# Backplane-2.net
KiCad netlist of a schematic drawn in EAGLE
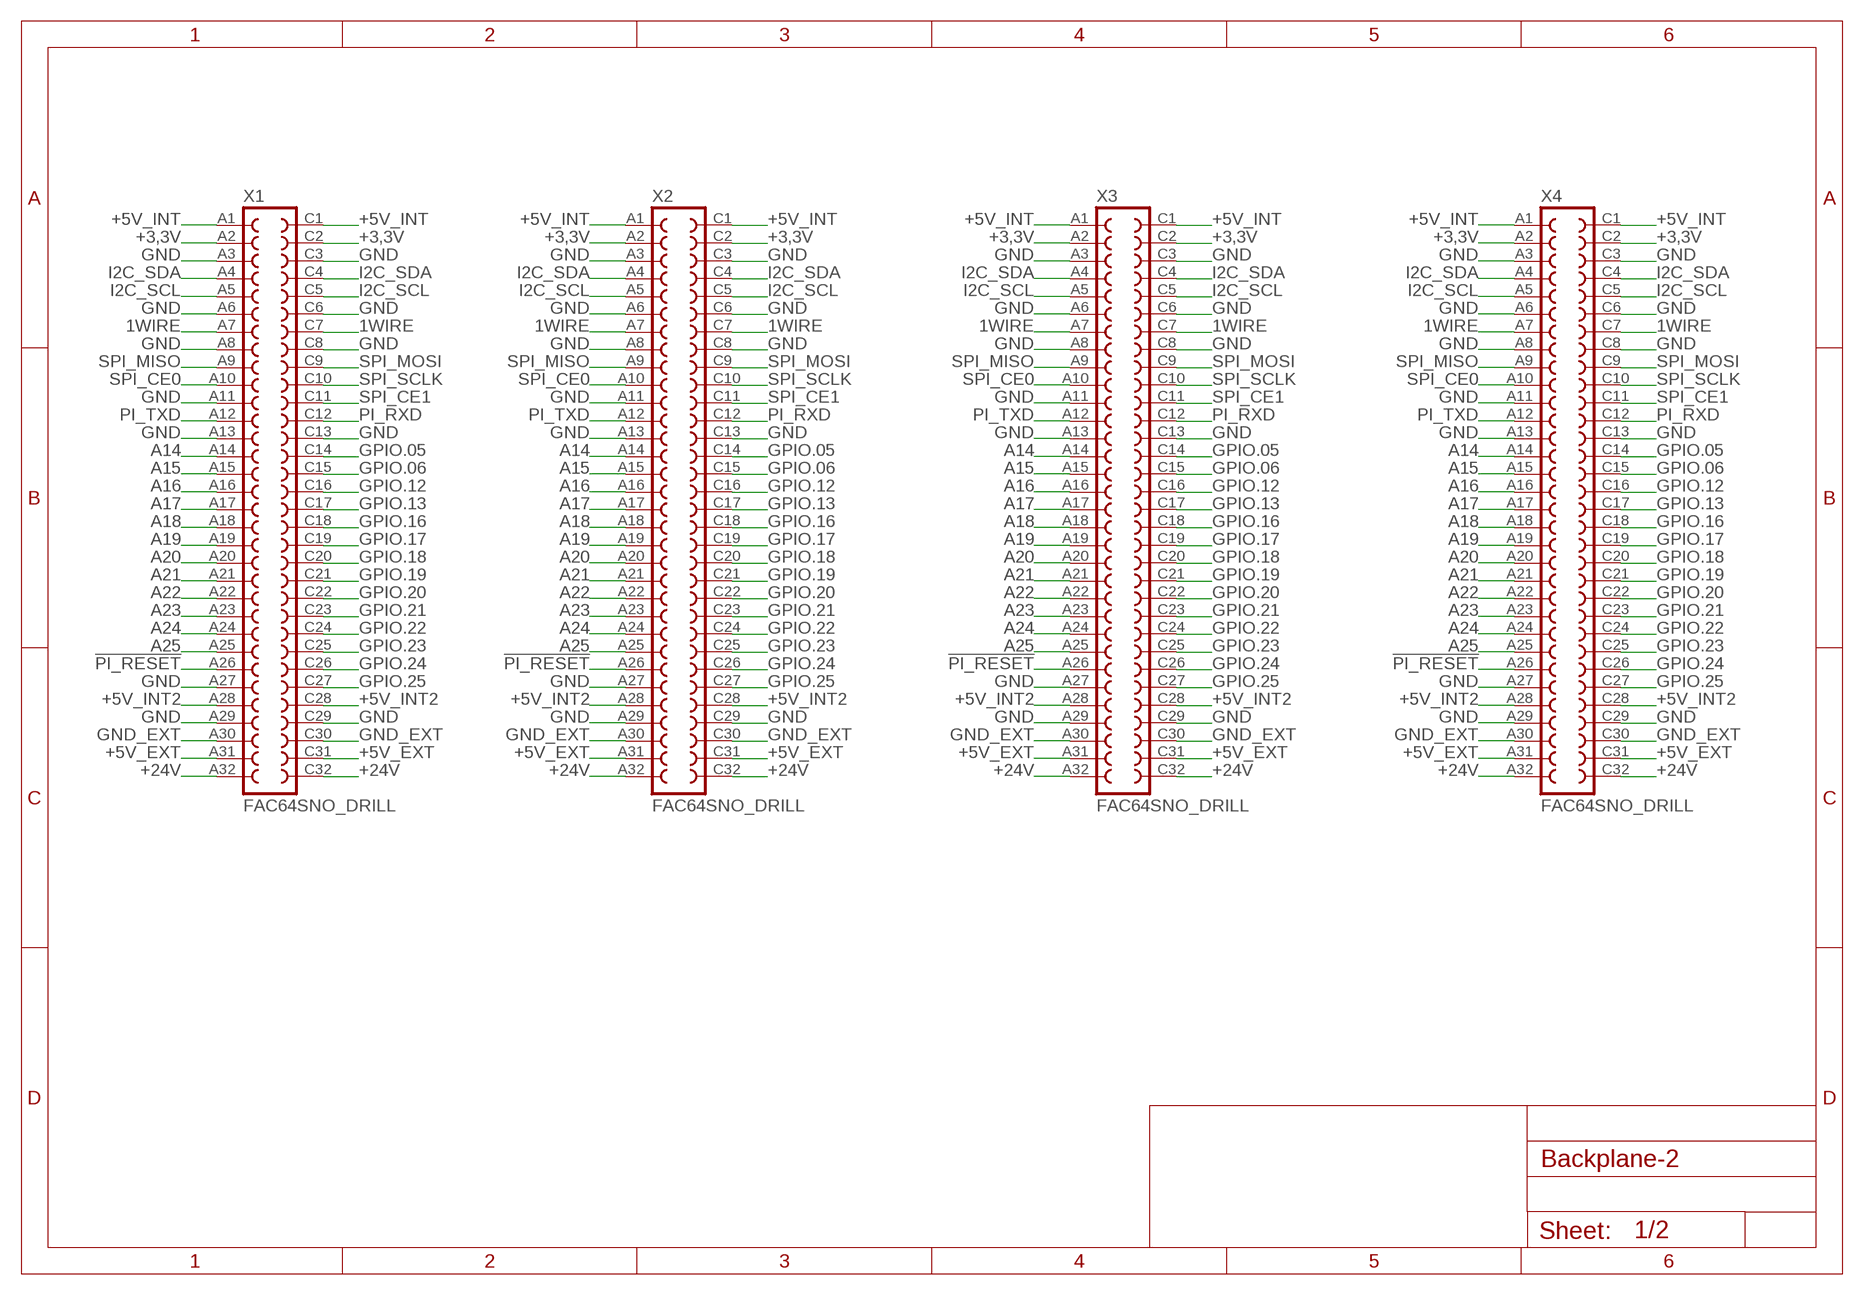
[diagram p0: schematic, sheet 1]
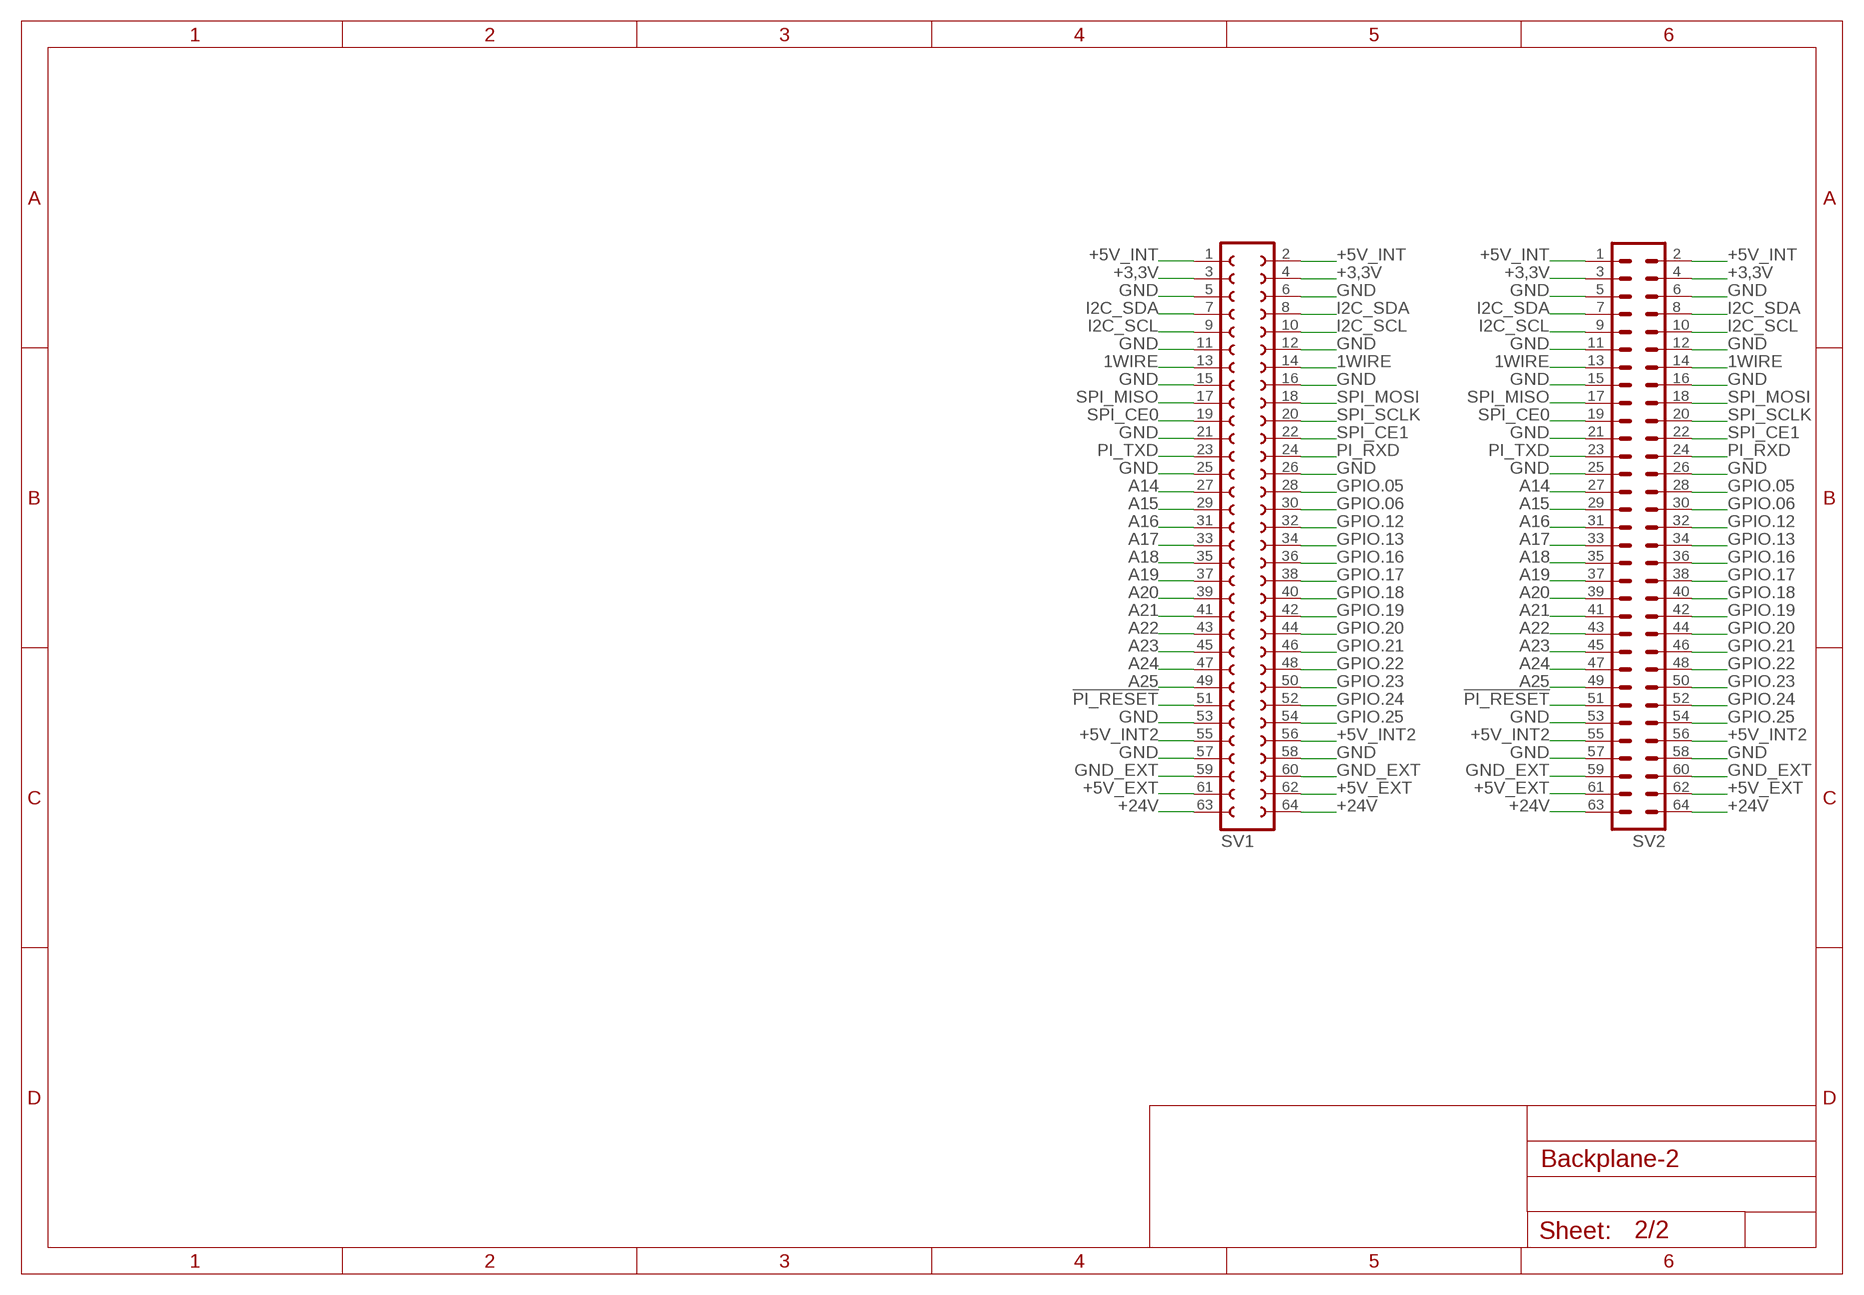
[diagram p1: schematic, sheet 2]

(export (version "E")
  (design (tool "Eeschema 10.0.6"))
  (components
    (comp (ref "SV1")
      (value "FE32-2W")
      (footprint "eagle-import:FE32-2W")
      (libsource (lib "eagle-import") (part "FE32-2W"))
    )
    (comp (ref "SV2")
      (value "MA32-2W")
      (footprint "eagle-import:MA32-2W")
      (libsource (lib "eagle-import") (part "MA32-2W"))
    )
    (comp (ref "X1")
      (value "FAC64SNO_DRILL")
      (footprint "eagle-import:FAC64S_NO_DRILL")
      (libsource (lib "eagle-import") (part "FAC64SNO_DRILL"))
    )
    (comp (ref "X2")
      (value "FAC64SNO_DRILL")
      (footprint "eagle-import:FAC64S_NO_DRILL")
      (libsource (lib "eagle-import") (part "FAC64SNO_DRILL"))
    )
    (comp (ref "X3")
      (value "FAC64SNO_DRILL")
      (footprint "eagle-import:FAC64S_NO_DRILL")
      (libsource (lib "eagle-import") (part "FAC64SNO_DRILL"))
    )
    (comp (ref "X4")
      (value "FAC64SNO_DRILL")
      (footprint "eagle-import:FAC64S_NO_DRILL")
      (libsource (lib "eagle-import") (part "FAC64SNO_DRILL"))
    )
  )
  (nets
    (net (code "1") (name "+3,3V") (class "Default")
      (node (ref "SV1") (pin "3") (pinfunction "3_3") (pintype "passive"))
      (node (ref "SV1") (pin "4") (pinfunction "4_4") (pintype "passive"))
      (node (ref "SV2") (pin "3") (pinfunction "3_3") (pintype "passive"))
      (node (ref "SV2") (pin "4") (pinfunction "4_4") (pintype "passive"))
      (node (ref "X1") (pin "A2") (pinfunction "A2_A2") (pintype "passive"))
      (node (ref "X1") (pin "C2") (pinfunction "C2_C2") (pintype "passive"))
      (node (ref "X2") (pin "A2") (pinfunction "A2_A2") (pintype "passive"))
      (node (ref "X2") (pin "C2") (pinfunction "C2_C2") (pintype "passive"))
      (node (ref "X3") (pin "A2") (pinfunction "A2_A2") (pintype "passive"))
      (node (ref "X3") (pin "C2") (pinfunction "C2_C2") (pintype "passive"))
      (node (ref "X4") (pin "A2") (pinfunction "A2_A2") (pintype "passive"))
      (node (ref "X4") (pin "C2") (pinfunction "C2_C2") (pintype "passive"))
    )
    (net (code "2") (name "+5V_EXT") (class "Default")
      (node (ref "SV1") (pin "61") (pinfunction "61_61") (pintype "passive"))
      (node (ref "SV1") (pin "62") (pinfunction "62_62") (pintype "passive"))
      (node (ref "SV2") (pin "61") (pinfunction "61_61") (pintype "passive"))
      (node (ref "SV2") (pin "62") (pinfunction "62_62") (pintype "passive"))
      (node (ref "X1") (pin "A31") (pinfunction "A31_A31") (pintype "passive"))
      (node (ref "X1") (pin "C31") (pinfunction "C31_C31") (pintype "passive"))
      (node (ref "X2") (pin "A31") (pinfunction "A31_A31") (pintype "passive"))
      (node (ref "X2") (pin "C31") (pinfunction "C31_C31") (pintype "passive"))
      (node (ref "X3") (pin "A31") (pinfunction "A31_A31") (pintype "passive"))
      (node (ref "X3") (pin "C31") (pinfunction "C31_C31") (pintype "passive"))
      (node (ref "X4") (pin "A31") (pinfunction "A31_A31") (pintype "passive"))
      (node (ref "X4") (pin "C31") (pinfunction "C31_C31") (pintype "passive"))
    )
    (net (code "3") (name "+5V_INT") (class "Default")
      (node (ref "SV1") (pin "1") (pinfunction "1_1") (pintype "passive"))
      (node (ref "SV1") (pin "2") (pinfunction "2_2") (pintype "passive"))
      (node (ref "SV2") (pin "1") (pinfunction "1_1") (pintype "passive"))
      (node (ref "SV2") (pin "2") (pinfunction "2_2") (pintype "passive"))
      (node (ref "X1") (pin "A1") (pinfunction "A1_A1") (pintype "passive"))
      (node (ref "X1") (pin "C1") (pinfunction "C1_C1") (pintype "passive"))
      (node (ref "X2") (pin "A1") (pinfunction "A1_A1") (pintype "passive"))
      (node (ref "X2") (pin "C1") (pinfunction "C1_C1") (pintype "passive"))
      (node (ref "X3") (pin "A1") (pinfunction "A1_A1") (pintype "passive"))
      (node (ref "X3") (pin "C1") (pinfunction "C1_C1") (pintype "passive"))
      (node (ref "X4") (pin "A1") (pinfunction "A1_A1") (pintype "passive"))
      (node (ref "X4") (pin "C1") (pinfunction "C1_C1") (pintype "passive"))
    )
    (net (code "4") (name "+5V_INT2") (class "Default")
      (node (ref "SV1") (pin "55") (pinfunction "55_55") (pintype "passive"))
      (node (ref "SV1") (pin "56") (pinfunction "56_56") (pintype "passive"))
      (node (ref "SV2") (pin "55") (pinfunction "55_55") (pintype "passive"))
      (node (ref "SV2") (pin "56") (pinfunction "56_56") (pintype "passive"))
      (node (ref "X1") (pin "A28") (pinfunction "A28_A28") (pintype "passive"))
      (node (ref "X1") (pin "C28") (pinfunction "C28_C28") (pintype "passive"))
      (node (ref "X2") (pin "A28") (pinfunction "A28_A28") (pintype "passive"))
      (node (ref "X2") (pin "C28") (pinfunction "C28_C28") (pintype "passive"))
      (node (ref "X3") (pin "A28") (pinfunction "A28_A28") (pintype "passive"))
      (node (ref "X3") (pin "C28") (pinfunction "C28_C28") (pintype "passive"))
      (node (ref "X4") (pin "A28") (pinfunction "A28_A28") (pintype "passive"))
      (node (ref "X4") (pin "C28") (pinfunction "C28_C28") (pintype "passive"))
    )
    (net (code "5") (name "+24V") (class "Default")
      (node (ref "SV1") (pin "63") (pinfunction "63_63") (pintype "passive"))
      (node (ref "SV1") (pin "64") (pinfunction "64_64") (pintype "passive"))
      (node (ref "SV2") (pin "63") (pinfunction "63_63") (pintype "passive"))
      (node (ref "SV2") (pin "64") (pinfunction "64_64") (pintype "passive"))
      (node (ref "X1") (pin "A32") (pinfunction "A32_A32") (pintype "passive"))
      (node (ref "X1") (pin "C32") (pinfunction "C32_C32") (pintype "passive"))
      (node (ref "X2") (pin "A32") (pinfunction "A32_A32") (pintype "passive"))
      (node (ref "X2") (pin "C32") (pinfunction "C32_C32") (pintype "passive"))
      (node (ref "X3") (pin "A32") (pinfunction "A32_A32") (pintype "passive"))
      (node (ref "X3") (pin "C32") (pinfunction "C32_C32") (pintype "passive"))
      (node (ref "X4") (pin "A32") (pinfunction "A32_A32") (pintype "passive"))
      (node (ref "X4") (pin "C32") (pinfunction "C32_C32") (pintype "passive"))
    )
    (net (code "6") (name "1WIRE") (class "Default")
      (node (ref "SV1") (pin "13") (pinfunction "13_13") (pintype "passive"))
      (node (ref "SV1") (pin "14") (pinfunction "14_14") (pintype "passive"))
      (node (ref "SV2") (pin "13") (pinfunction "13_13") (pintype "passive"))
      (node (ref "SV2") (pin "14") (pinfunction "14_14") (pintype "passive"))
      (node (ref "X1") (pin "A7") (pinfunction "A7_A7") (pintype "passive"))
      (node (ref "X1") (pin "C7") (pinfunction "C7_C7") (pintype "passive"))
      (node (ref "X2") (pin "A7") (pinfunction "A7_A7") (pintype "passive"))
      (node (ref "X2") (pin "C7") (pinfunction "C7_C7") (pintype "passive"))
      (node (ref "X3") (pin "A7") (pinfunction "A7_A7") (pintype "passive"))
      (node (ref "X3") (pin "C7") (pinfunction "C7_C7") (pintype "passive"))
      (node (ref "X4") (pin "A7") (pinfunction "A7_A7") (pintype "passive"))
      (node (ref "X4") (pin "C7") (pinfunction "C7_C7") (pintype "passive"))
    )
    (net (code "7") (name "A14") (class "Default")
      (node (ref "SV1") (pin "27") (pinfunction "27_27") (pintype "passive"))
      (node (ref "SV2") (pin "27") (pinfunction "27_27") (pintype "passive"))
      (node (ref "X1") (pin "A14") (pinfunction "A14_A14") (pintype "passive"))
      (node (ref "X2") (pin "A14") (pinfunction "A14_A14") (pintype "passive"))
      (node (ref "X3") (pin "A14") (pinfunction "A14_A14") (pintype "passive"))
      (node (ref "X4") (pin "A14") (pinfunction "A14_A14") (pintype "passive"))
    )
    (net (code "8") (name "A15") (class "Default")
      (node (ref "SV1") (pin "29") (pinfunction "29_29") (pintype "passive"))
      (node (ref "SV2") (pin "29") (pinfunction "29_29") (pintype "passive"))
      (node (ref "X1") (pin "A15") (pinfunction "A15_A15") (pintype "passive"))
      (node (ref "X2") (pin "A15") (pinfunction "A15_A15") (pintype "passive"))
      (node (ref "X3") (pin "A15") (pinfunction "A15_A15") (pintype "passive"))
      (node (ref "X4") (pin "A15") (pinfunction "A15_A15") (pintype "passive"))
    )
    (net (code "9") (name "A16") (class "Default")
      (node (ref "SV1") (pin "31") (pinfunction "31_31") (pintype "passive"))
      (node (ref "SV2") (pin "31") (pinfunction "31_31") (pintype "passive"))
      (node (ref "X1") (pin "A16") (pinfunction "A16_A16") (pintype "passive"))
      (node (ref "X2") (pin "A16") (pinfunction "A16_A16") (pintype "passive"))
      (node (ref "X3") (pin "A16") (pinfunction "A16_A16") (pintype "passive"))
      (node (ref "X4") (pin "A16") (pinfunction "A16_A16") (pintype "passive"))
    )
    (net (code "10") (name "A17") (class "Default")
      (node (ref "SV1") (pin "33") (pinfunction "33_33") (pintype "passive"))
      (node (ref "SV2") (pin "33") (pinfunction "33_33") (pintype "passive"))
      (node (ref "X1") (pin "A17") (pinfunction "A17_A17") (pintype "passive"))
      (node (ref "X2") (pin "A17") (pinfunction "A17_A17") (pintype "passive"))
      (node (ref "X3") (pin "A17") (pinfunction "A17_A17") (pintype "passive"))
      (node (ref "X4") (pin "A17") (pinfunction "A17_A17") (pintype "passive"))
    )
    (net (code "11") (name "A18") (class "Default")
      (node (ref "SV1") (pin "35") (pinfunction "35_35") (pintype "passive"))
      (node (ref "SV2") (pin "35") (pinfunction "35_35") (pintype "passive"))
      (node (ref "X1") (pin "A18") (pinfunction "A18_A18") (pintype "passive"))
      (node (ref "X2") (pin "A18") (pinfunction "A18_A18") (pintype "passive"))
      (node (ref "X3") (pin "A18") (pinfunction "A18_A18") (pintype "passive"))
      (node (ref "X4") (pin "A18") (pinfunction "A18_A18") (pintype "passive"))
    )
    (net (code "12") (name "A19") (class "Default")
      (node (ref "SV1") (pin "37") (pinfunction "37_37") (pintype "passive"))
      (node (ref "SV2") (pin "37") (pinfunction "37_37") (pintype "passive"))
      (node (ref "X1") (pin "A19") (pinfunction "A19_A19") (pintype "passive"))
      (node (ref "X2") (pin "A19") (pinfunction "A19_A19") (pintype "passive"))
      (node (ref "X3") (pin "A19") (pinfunction "A19_A19") (pintype "passive"))
      (node (ref "X4") (pin "A19") (pinfunction "A19_A19") (pintype "passive"))
    )
    (net (code "13") (name "A20") (class "Default")
      (node (ref "SV1") (pin "39") (pinfunction "39_39") (pintype "passive"))
      (node (ref "SV2") (pin "39") (pinfunction "39_39") (pintype "passive"))
      (node (ref "X1") (pin "A20") (pinfunction "A20_A20") (pintype "passive"))
      (node (ref "X2") (pin "A20") (pinfunction "A20_A20") (pintype "passive"))
      (node (ref "X3") (pin "A20") (pinfunction "A20_A20") (pintype "passive"))
      (node (ref "X4") (pin "A20") (pinfunction "A20_A20") (pintype "passive"))
    )
    (net (code "14") (name "A21") (class "Default")
      (node (ref "SV1") (pin "41") (pinfunction "41_41") (pintype "passive"))
      (node (ref "SV2") (pin "41") (pinfunction "41_41") (pintype "passive"))
      (node (ref "X1") (pin "A21") (pinfunction "A21_A21") (pintype "passive"))
      (node (ref "X2") (pin "A21") (pinfunction "A21_A21") (pintype "passive"))
      (node (ref "X3") (pin "A21") (pinfunction "A21_A21") (pintype "passive"))
      (node (ref "X4") (pin "A21") (pinfunction "A21_A21") (pintype "passive"))
    )
    (net (code "15") (name "A22") (class "Default")
      (node (ref "SV1") (pin "43") (pinfunction "43_43") (pintype "passive"))
      (node (ref "SV2") (pin "43") (pinfunction "43_43") (pintype "passive"))
      (node (ref "X1") (pin "A22") (pinfunction "A22_A22") (pintype "passive"))
      (node (ref "X2") (pin "A22") (pinfunction "A22_A22") (pintype "passive"))
      (node (ref "X3") (pin "A22") (pinfunction "A22_A22") (pintype "passive"))
      (node (ref "X4") (pin "A22") (pinfunction "A22_A22") (pintype "passive"))
    )
    (net (code "16") (name "A23") (class "Default")
      (node (ref "SV1") (pin "45") (pinfunction "45_45") (pintype "passive"))
      (node (ref "SV2") (pin "45") (pinfunction "45_45") (pintype "passive"))
      (node (ref "X1") (pin "A23") (pinfunction "A23_A23") (pintype "passive"))
      (node (ref "X2") (pin "A23") (pinfunction "A23_A23") (pintype "passive"))
      (node (ref "X3") (pin "A23") (pinfunction "A23_A23") (pintype "passive"))
      (node (ref "X4") (pin "A23") (pinfunction "A23_A23") (pintype "passive"))
    )
    (net (code "17") (name "A24") (class "Default")
      (node (ref "SV1") (pin "47") (pinfunction "47_47") (pintype "passive"))
      (node (ref "SV2") (pin "47") (pinfunction "47_47") (pintype "passive"))
      (node (ref "X1") (pin "A24") (pinfunction "A24_A24") (pintype "passive"))
      (node (ref "X2") (pin "A24") (pinfunction "A24_A24") (pintype "passive"))
      (node (ref "X3") (pin "A24") (pinfunction "A24_A24") (pintype "passive"))
      (node (ref "X4") (pin "A24") (pinfunction "A24_A24") (pintype "passive"))
    )
    (net (code "18") (name "A25") (class "Default")
      (node (ref "SV1") (pin "49") (pinfunction "49_49") (pintype "passive"))
      (node (ref "SV2") (pin "49") (pinfunction "49_49") (pintype "passive"))
      (node (ref "X1") (pin "A25") (pinfunction "A25_A25") (pintype "passive"))
      (node (ref "X2") (pin "A25") (pinfunction "A25_A25") (pintype "passive"))
      (node (ref "X3") (pin "A25") (pinfunction "A25_A25") (pintype "passive"))
      (node (ref "X4") (pin "A25") (pinfunction "A25_A25") (pintype "passive"))
    )
    (net (code "19") (name "GND") (class "Default")
      (node (ref "SV1") (pin "11") (pinfunction "11_11") (pintype "passive"))
      (node (ref "SV1") (pin "12") (pinfunction "12_12") (pintype "passive"))
      (node (ref "SV1") (pin "15") (pinfunction "15_15") (pintype "passive"))
      (node (ref "SV1") (pin "16") (pinfunction "16_16") (pintype "passive"))
      (node (ref "SV1") (pin "21") (pinfunction "21_21") (pintype "passive"))
      (node (ref "SV1") (pin "25") (pinfunction "25_25") (pintype "passive"))
      (node (ref "SV1") (pin "26") (pinfunction "26_26") (pintype "passive"))
      (node (ref "SV1") (pin "5") (pinfunction "5_5") (pintype "passive"))
      (node (ref "SV1") (pin "53") (pinfunction "53_53") (pintype "passive"))
      (node (ref "SV1") (pin "57") (pinfunction "57_57") (pintype "passive"))
      (node (ref "SV1") (pin "58") (pinfunction "58_58") (pintype "passive"))
      (node (ref "SV1") (pin "6") (pinfunction "6_6") (pintype "passive"))
      (node (ref "SV2") (pin "11") (pinfunction "11_11") (pintype "passive"))
      (node (ref "SV2") (pin "12") (pinfunction "12_12") (pintype "passive"))
      (node (ref "SV2") (pin "15") (pinfunction "15_15") (pintype "passive"))
      (node (ref "SV2") (pin "16") (pinfunction "16_16") (pintype "passive"))
      (node (ref "SV2") (pin "21") (pinfunction "21_21") (pintype "passive"))
      (node (ref "SV2") (pin "25") (pinfunction "25_25") (pintype "passive"))
      (node (ref "SV2") (pin "26") (pinfunction "26_26") (pintype "passive"))
      (node (ref "SV2") (pin "5") (pinfunction "5_5") (pintype "passive"))
      (node (ref "SV2") (pin "53") (pinfunction "53_53") (pintype "passive"))
      (node (ref "SV2") (pin "57") (pinfunction "57_57") (pintype "passive"))
      (node (ref "SV2") (pin "58") (pinfunction "58_58") (pintype "passive"))
      (node (ref "SV2") (pin "6") (pinfunction "6_6") (pintype "passive"))
      (node (ref "X1") (pin "A11") (pinfunction "A11_A11") (pintype "passive"))
      (node (ref "X1") (pin "A13") (pinfunction "A13_A13") (pintype "passive"))
      (node (ref "X1") (pin "A27") (pinfunction "A27_A27") (pintype "passive"))
      (node (ref "X1") (pin "A29") (pinfunction "A29_A29") (pintype "passive"))
      (node (ref "X1") (pin "A3") (pinfunction "A3_A3") (pintype "passive"))
      (node (ref "X1") (pin "A6") (pinfunction "A6_A6") (pintype "passive"))
      (node (ref "X1") (pin "A8") (pinfunction "A8_A8") (pintype "passive"))
      (node (ref "X1") (pin "C13") (pinfunction "C13_C13") (pintype "passive"))
      (node (ref "X1") (pin "C29") (pinfunction "C29_C29") (pintype "passive"))
      (node (ref "X1") (pin "C3") (pinfunction "C3_C3") (pintype "passive"))
      (node (ref "X1") (pin "C6") (pinfunction "C6_C6") (pintype "passive"))
      (node (ref "X1") (pin "C8") (pinfunction "C8_C8") (pintype "passive"))
      (node (ref "X2") (pin "A11") (pinfunction "A11_A11") (pintype "passive"))
      (node (ref "X2") (pin "A13") (pinfunction "A13_A13") (pintype "passive"))
      (node (ref "X2") (pin "A27") (pinfunction "A27_A27") (pintype "passive"))
      (node (ref "X2") (pin "A29") (pinfunction "A29_A29") (pintype "passive"))
      (node (ref "X2") (pin "A3") (pinfunction "A3_A3") (pintype "passive"))
      (node (ref "X2") (pin "A6") (pinfunction "A6_A6") (pintype "passive"))
      (node (ref "X2") (pin "A8") (pinfunction "A8_A8") (pintype "passive"))
      (node (ref "X2") (pin "C13") (pinfunction "C13_C13") (pintype "passive"))
      (node (ref "X2") (pin "C29") (pinfunction "C29_C29") (pintype "passive"))
      (node (ref "X2") (pin "C3") (pinfunction "C3_C3") (pintype "passive"))
      (node (ref "X2") (pin "C6") (pinfunction "C6_C6") (pintype "passive"))
      (node (ref "X2") (pin "C8") (pinfunction "C8_C8") (pintype "passive"))
      (node (ref "X3") (pin "A11") (pinfunction "A11_A11") (pintype "passive"))
      (node (ref "X3") (pin "A13") (pinfunction "A13_A13") (pintype "passive"))
      (node (ref "X3") (pin "A27") (pinfunction "A27_A27") (pintype "passive"))
      (node (ref "X3") (pin "A29") (pinfunction "A29_A29") (pintype "passive"))
      (node (ref "X3") (pin "A3") (pinfunction "A3_A3") (pintype "passive"))
      (node (ref "X3") (pin "A6") (pinfunction "A6_A6") (pintype "passive"))
      (node (ref "X3") (pin "A8") (pinfunction "A8_A8") (pintype "passive"))
      (node (ref "X3") (pin "C13") (pinfunction "C13_C13") (pintype "passive"))
      (node (ref "X3") (pin "C29") (pinfunction "C29_C29") (pintype "passive"))
      (node (ref "X3") (pin "C3") (pinfunction "C3_C3") (pintype "passive"))
      (node (ref "X3") (pin "C6") (pinfunction "C6_C6") (pintype "passive"))
      (node (ref "X3") (pin "C8") (pinfunction "C8_C8") (pintype "passive"))
      (node (ref "X4") (pin "A11") (pinfunction "A11_A11") (pintype "passive"))
      (node (ref "X4") (pin "A13") (pinfunction "A13_A13") (pintype "passive"))
      (node (ref "X4") (pin "A27") (pinfunction "A27_A27") (pintype "passive"))
      (node (ref "X4") (pin "A29") (pinfunction "A29_A29") (pintype "passive"))
      (node (ref "X4") (pin "A3") (pinfunction "A3_A3") (pintype "passive"))
      (node (ref "X4") (pin "A6") (pinfunction "A6_A6") (pintype "passive"))
      (node (ref "X4") (pin "A8") (pinfunction "A8_A8") (pintype "passive"))
      (node (ref "X4") (pin "C13") (pinfunction "C13_C13") (pintype "passive"))
      (node (ref "X4") (pin "C29") (pinfunction "C29_C29") (pintype "passive"))
      (node (ref "X4") (pin "C3") (pinfunction "C3_C3") (pintype "passive"))
      (node (ref "X4") (pin "C6") (pinfunction "C6_C6") (pintype "passive"))
      (node (ref "X4") (pin "C8") (pinfunction "C8_C8") (pintype "passive"))
    )
    (net (code "20") (name "GND_EXT") (class "Default")
      (node (ref "SV1") (pin "59") (pinfunction "59_59") (pintype "passive"))
      (node (ref "SV1") (pin "60") (pinfunction "60_60") (pintype "passive"))
      (node (ref "SV2") (pin "59") (pinfunction "59_59") (pintype "passive"))
      (node (ref "SV2") (pin "60") (pinfunction "60_60") (pintype "passive"))
      (node (ref "X1") (pin "A30") (pinfunction "A30_A30") (pintype "passive"))
      (node (ref "X1") (pin "C30") (pinfunction "C30_C30") (pintype "passive"))
      (node (ref "X2") (pin "A30") (pinfunction "A30_A30") (pintype "passive"))
      (node (ref "X2") (pin "C30") (pinfunction "C30_C30") (pintype "passive"))
      (node (ref "X3") (pin "A30") (pinfunction "A30_A30") (pintype "passive"))
      (node (ref "X3") (pin "C30") (pinfunction "C30_C30") (pintype "passive"))
      (node (ref "X4") (pin "A30") (pinfunction "A30_A30") (pintype "passive"))
      (node (ref "X4") (pin "C30") (pinfunction "C30_C30") (pintype "passive"))
    )
    (net (code "21") (name "GPIO.05") (class "Default")
      (node (ref "SV1") (pin "28") (pinfunction "28_28") (pintype "passive"))
      (node (ref "SV2") (pin "28") (pinfunction "28_28") (pintype "passive"))
      (node (ref "X1") (pin "C14") (pinfunction "C14_C14") (pintype "passive"))
      (node (ref "X2") (pin "C14") (pinfunction "C14_C14") (pintype "passive"))
      (node (ref "X3") (pin "C14") (pinfunction "C14_C14") (pintype "passive"))
      (node (ref "X4") (pin "C14") (pinfunction "C14_C14") (pintype "passive"))
    )
    (net (code "22") (name "GPIO.06") (class "Default")
      (node (ref "SV1") (pin "30") (pinfunction "30_30") (pintype "passive"))
      (node (ref "SV2") (pin "30") (pinfunction "30_30") (pintype "passive"))
      (node (ref "X1") (pin "C15") (pinfunction "C15_C15") (pintype "passive"))
      (node (ref "X2") (pin "C15") (pinfunction "C15_C15") (pintype "passive"))
      (node (ref "X3") (pin "C15") (pinfunction "C15_C15") (pintype "passive"))
      (node (ref "X4") (pin "C15") (pinfunction "C15_C15") (pintype "passive"))
    )
    (net (code "23") (name "GPIO.12") (class "Default")
      (node (ref "SV1") (pin "32") (pinfunction "32_32") (pintype "passive"))
      (node (ref "SV2") (pin "32") (pinfunction "32_32") (pintype "passive"))
      (node (ref "X1") (pin "C16") (pinfunction "C16_C16") (pintype "passive"))
      (node (ref "X2") (pin "C16") (pinfunction "C16_C16") (pintype "passive"))
      (node (ref "X3") (pin "C16") (pinfunction "C16_C16") (pintype "passive"))
      (node (ref "X4") (pin "C16") (pinfunction "C16_C16") (pintype "passive"))
    )
    (net (code "24") (name "GPIO.13") (class "Default")
      (node (ref "SV1") (pin "34") (pinfunction "34_34") (pintype "passive"))
      (node (ref "SV2") (pin "34") (pinfunction "34_34") (pintype "passive"))
      (node (ref "X1") (pin "C17") (pinfunction "C17_C17") (pintype "passive"))
      (node (ref "X2") (pin "C17") (pinfunction "C17_C17") (pintype "passive"))
      (node (ref "X3") (pin "C17") (pinfunction "C17_C17") (pintype "passive"))
      (node (ref "X4") (pin "C17") (pinfunction "C17_C17") (pintype "passive"))
    )
    (net (code "25") (name "GPIO.16") (class "Default")
      (node (ref "SV1") (pin "36") (pinfunction "36_36") (pintype "passive"))
      (node (ref "SV2") (pin "36") (pinfunction "36_36") (pintype "passive"))
      (node (ref "X1") (pin "C18") (pinfunction "C18_C18") (pintype "passive"))
      (node (ref "X2") (pin "C18") (pinfunction "C18_C18") (pintype "passive"))
      (node (ref "X3") (pin "C18") (pinfunction "C18_C18") (pintype "passive"))
      (node (ref "X4") (pin "C18") (pinfunction "C18_C18") (pintype "passive"))
    )
    (net (code "26") (name "GPIO.17") (class "Default")
      (node (ref "SV1") (pin "38") (pinfunction "38_38") (pintype "passive"))
      (node (ref "SV2") (pin "38") (pinfunction "38_38") (pintype "passive"))
      (node (ref "X1") (pin "C19") (pinfunction "C19_C19") (pintype "passive"))
      (node (ref "X2") (pin "C19") (pinfunction "C19_C19") (pintype "passive"))
      (node (ref "X3") (pin "C19") (pinfunction "C19_C19") (pintype "passive"))
      (node (ref "X4") (pin "C19") (pinfunction "C19_C19") (pintype "passive"))
    )
    (net (code "27") (name "GPIO.18") (class "Default")
      (node (ref "SV1") (pin "40") (pinfunction "40_40") (pintype "passive"))
      (node (ref "SV2") (pin "40") (pinfunction "40_40") (pintype "passive"))
      (node (ref "X1") (pin "C20") (pinfunction "C20_C20") (pintype "passive"))
      (node (ref "X2") (pin "C20") (pinfunction "C20_C20") (pintype "passive"))
      (node (ref "X3") (pin "C20") (pinfunction "C20_C20") (pintype "passive"))
      (node (ref "X4") (pin "C20") (pinfunction "C20_C20") (pintype "passive"))
    )
    (net (code "28") (name "GPIO.19") (class "Default")
      (node (ref "SV1") (pin "42") (pinfunction "42_42") (pintype "passive"))
      (node (ref "SV2") (pin "42") (pinfunction "42_42") (pintype "passive"))
      (node (ref "X1") (pin "C21") (pinfunction "C21_C21") (pintype "passive"))
      (node (ref "X2") (pin "C21") (pinfunction "C21_C21") (pintype "passive"))
      (node (ref "X3") (pin "C21") (pinfunction "C21_C21") (pintype "passive"))
      (node (ref "X4") (pin "C21") (pinfunction "C21_C21") (pintype "passive"))
    )
    (net (code "29") (name "GPIO.20") (class "Default")
      (node (ref "SV1") (pin "44") (pinfunction "44_44") (pintype "passive"))
      (node (ref "SV2") (pin "44") (pinfunction "44_44") (pintype "passive"))
      (node (ref "X1") (pin "C22") (pinfunction "C22_C22") (pintype "passive"))
      (node (ref "X2") (pin "C22") (pinfunction "C22_C22") (pintype "passive"))
      (node (ref "X3") (pin "C22") (pinfunction "C22_C22") (pintype "passive"))
      (node (ref "X4") (pin "C22") (pinfunction "C22_C22") (pintype "passive"))
    )
    (net (code "30") (name "GPIO.21") (class "Default")
      (node (ref "SV1") (pin "46") (pinfunction "46_46") (pintype "passive"))
      (node (ref "SV2") (pin "46") (pinfunction "46_46") (pintype "passive"))
      (node (ref "X1") (pin "C23") (pinfunction "C23_C23") (pintype "passive"))
      (node (ref "X2") (pin "C23") (pinfunction "C23_C23") (pintype "passive"))
      (node (ref "X3") (pin "C23") (pinfunction "C23_C23") (pintype "passive"))
      (node (ref "X4") (pin "C23") (pinfunction "C23_C23") (pintype "passive"))
    )
    (net (code "31") (name "GPIO.22") (class "Default")
      (node (ref "SV1") (pin "48") (pinfunction "48_48") (pintype "passive"))
      (node (ref "SV2") (pin "48") (pinfunction "48_48") (pintype "passive"))
      (node (ref "X1") (pin "C24") (pinfunction "C24_C24") (pintype "passive"))
      (node (ref "X2") (pin "C24") (pinfunction "C24_C24") (pintype "passive"))
      (node (ref "X3") (pin "C24") (pinfunction "C24_C24") (pintype "passive"))
      (node (ref "X4") (pin "C24") (pinfunction "C24_C24") (pintype "passive"))
    )
    (net (code "32") (name "GPIO.23") (class "Default")
      (node (ref "SV1") (pin "50") (pinfunction "50_50") (pintype "passive"))
      (node (ref "SV2") (pin "50") (pinfunction "50_50") (pintype "passive"))
      (node (ref "X1") (pin "C25") (pinfunction "C25_C25") (pintype "passive"))
      (node (ref "X2") (pin "C25") (pinfunction "C25_C25") (pintype "passive"))
      (node (ref "X3") (pin "C25") (pinfunction "C25_C25") (pintype "passive"))
      (node (ref "X4") (pin "C25") (pinfunction "C25_C25") (pintype "passive"))
    )
    (net (code "33") (name "GPIO.24") (class "Default")
      (node (ref "SV1") (pin "52") (pinfunction "52_52") (pintype "passive"))
      (node (ref "SV2") (pin "52") (pinfunction "52_52") (pintype "passive"))
      (node (ref "X1") (pin "C26") (pinfunction "C26_C26") (pintype "passive"))
      (node (ref "X2") (pin "C26") (pinfunction "C26_C26") (pintype "passive"))
      (node (ref "X3") (pin "C26") (pinfunction "C26_C26") (pintype "passive"))
      (node (ref "X4") (pin "C26") (pinfunction "C26_C26") (pintype "passive"))
    )
    (net (code "34") (name "GPIO.25") (class "Default")
      (node (ref "SV1") (pin "54") (pinfunction "54_54") (pintype "passive"))
      (node (ref "SV2") (pin "54") (pinfunction "54_54") (pintype "passive"))
      (node (ref "X1") (pin "C27") (pinfunction "C27_C27") (pintype "passive"))
      (node (ref "X2") (pin "C27") (pinfunction "C27_C27") (pintype "passive"))
      (node (ref "X3") (pin "C27") (pinfunction "C27_C27") (pintype "passive"))
      (node (ref "X4") (pin "C27") (pinfunction "C27_C27") (pintype "passive"))
    )
    (net (code "35") (name "I2C_SCL") (class "Default")
      (node (ref "SV1") (pin "10") (pinfunction "10_10") (pintype "passive"))
      (node (ref "SV1") (pin "9") (pinfunction "9_9") (pintype "passive"))
      (node (ref "SV2") (pin "10") (pinfunction "10_10") (pintype "passive"))
      (node (ref "SV2") (pin "9") (pinfunction "9_9") (pintype "passive"))
      (node (ref "X1") (pin "A5") (pinfunction "A5_A5") (pintype "passive"))
      (node (ref "X1") (pin "C5") (pinfunction "C5_C5") (pintype "passive"))
      (node (ref "X2") (pin "A5") (pinfunction "A5_A5") (pintype "passive"))
      (node (ref "X2") (pin "C5") (pinfunction "C5_C5") (pintype "passive"))
      (node (ref "X3") (pin "A5") (pinfunction "A5_A5") (pintype "passive"))
      (node (ref "X3") (pin "C5") (pinfunction "C5_C5") (pintype "passive"))
      (node (ref "X4") (pin "A5") (pinfunction "A5_A5") (pintype "passive"))
      (node (ref "X4") (pin "C5") (pinfunction "C5_C5") (pintype "passive"))
    )
    (net (code "36") (name "I2C_SDA") (class "Default")
      (node (ref "SV1") (pin "7") (pinfunction "7_7") (pintype "passive"))
      (node (ref "SV1") (pin "8") (pinfunction "8_8") (pintype "passive"))
      (node (ref "SV2") (pin "7") (pinfunction "7_7") (pintype "passive"))
      (node (ref "SV2") (pin "8") (pinfunction "8_8") (pintype "passive"))
      (node (ref "X1") (pin "A4") (pinfunction "A4_A4") (pintype "passive"))
      (node (ref "X1") (pin "C4") (pinfunction "C4_C4") (pintype "passive"))
      (node (ref "X2") (pin "A4") (pinfunction "A4_A4") (pintype "passive"))
      (node (ref "X2") (pin "C4") (pinfunction "C4_C4") (pintype "passive"))
      (node (ref "X3") (pin "A4") (pinfunction "A4_A4") (pintype "passive"))
      (node (ref "X3") (pin "C4") (pinfunction "C4_C4") (pintype "passive"))
      (node (ref "X4") (pin "A4") (pinfunction "A4_A4") (pintype "passive"))
      (node (ref "X4") (pin "C4") (pinfunction "C4_C4") (pintype "passive"))
    )
    (net (code "37") (name "PI_RXD") (class "Default")
      (node (ref "SV1") (pin "24") (pinfunction "24_24") (pintype "passive"))
      (node (ref "SV2") (pin "24") (pinfunction "24_24") (pintype "passive"))
      (node (ref "X1") (pin "C12") (pinfunction "C12_C12") (pintype "passive"))
      (node (ref "X2") (pin "C12") (pinfunction "C12_C12") (pintype "passive"))
      (node (ref "X3") (pin "C12") (pinfunction "C12_C12") (pintype "passive"))
      (node (ref "X4") (pin "C12") (pinfunction "C12_C12") (pintype "passive"))
    )
    (net (code "38") (name "PI_TXD") (class "Default")
      (node (ref "SV1") (pin "23") (pinfunction "23_23") (pintype "passive"))
      (node (ref "SV2") (pin "23") (pinfunction "23_23") (pintype "passive"))
      (node (ref "X1") (pin "A12") (pinfunction "A12_A12") (pintype "passive"))
      (node (ref "X2") (pin "A12") (pinfunction "A12_A12") (pintype "passive"))
      (node (ref "X3") (pin "A12") (pinfunction "A12_A12") (pintype "passive"))
      (node (ref "X4") (pin "A12") (pinfunction "A12_A12") (pintype "passive"))
    )
    (net (code "39") (name "SPI_CE0") (class "Default")
      (node (ref "SV1") (pin "19") (pinfunction "19_19") (pintype "passive"))
      (node (ref "SV2") (pin "19") (pinfunction "19_19") (pintype "passive"))
      (node (ref "X1") (pin "A10") (pinfunction "A10_A10") (pintype "passive"))
      (node (ref "X2") (pin "A10") (pinfunction "A10_A10") (pintype "passive"))
      (node (ref "X3") (pin "A10") (pinfunction "A10_A10") (pintype "passive"))
      (node (ref "X4") (pin "A10") (pinfunction "A10_A10") (pintype "passive"))
    )
    (net (code "40") (name "SPI_CE1") (class "Default")
      (node (ref "SV1") (pin "22") (pinfunction "22_22") (pintype "passive"))
      (node (ref "SV2") (pin "22") (pinfunction "22_22") (pintype "passive"))
      (node (ref "X1") (pin "C11") (pinfunction "C11_C11") (pintype "passive"))
      (node (ref "X2") (pin "C11") (pinfunction "C11_C11") (pintype "passive"))
      (node (ref "X3") (pin "C11") (pinfunction "C11_C11") (pintype "passive"))
      (node (ref "X4") (pin "C11") (pinfunction "C11_C11") (pintype "passive"))
    )
    (net (code "41") (name "SPI_MISO") (class "Default")
      (node (ref "SV1") (pin "17") (pinfunction "17_17") (pintype "passive"))
      (node (ref "SV2") (pin "17") (pinfunction "17_17") (pintype "passive"))
      (node (ref "X1") (pin "A9") (pinfunction "A9_A9") (pintype "passive"))
      (node (ref "X2") (pin "A9") (pinfunction "A9_A9") (pintype "passive"))
      (node (ref "X3") (pin "A9") (pinfunction "A9_A9") (pintype "passive"))
      (node (ref "X4") (pin "A9") (pinfunction "A9_A9") (pintype "passive"))
    )
    (net (code "42") (name "SPI_MOSI") (class "Default")
      (node (ref "SV1") (pin "18") (pinfunction "18_18") (pintype "passive"))
      (node (ref "SV2") (pin "18") (pinfunction "18_18") (pintype "passive"))
      (node (ref "X1") (pin "C9") (pinfunction "C9_C9") (pintype "passive"))
      (node (ref "X2") (pin "C9") (pinfunction "C9_C9") (pintype "passive"))
      (node (ref "X3") (pin "C9") (pinfunction "C9_C9") (pintype "passive"))
      (node (ref "X4") (pin "C9") (pinfunction "C9_C9") (pintype "passive"))
    )
    (net (code "43") (name "SPI_SCLK") (class "Default")
      (node (ref "SV1") (pin "20") (pinfunction "20_20") (pintype "passive"))
      (node (ref "SV2") (pin "20") (pinfunction "20_20") (pintype "passive"))
      (node (ref "X1") (pin "C10") (pinfunction "C10_C10") (pintype "passive"))
      (node (ref "X2") (pin "C10") (pinfunction "C10_C10") (pintype "passive"))
      (node (ref "X3") (pin "C10") (pinfunction "C10_C10") (pintype "passive"))
      (node (ref "X4") (pin "C10") (pinfunction "C10_C10") (pintype "passive"))
    )
    (net (code "44") (name "~{PI_RESET}") (class "Default")
      (node (ref "SV1") (pin "51") (pinfunction "51_51") (pintype "passive"))
      (node (ref "SV2") (pin "51") (pinfunction "51_51") (pintype "passive"))
      (node (ref "X1") (pin "A26") (pinfunction "A26_A26") (pintype "passive"))
      (node (ref "X2") (pin "A26") (pinfunction "A26_A26") (pintype "passive"))
      (node (ref "X3") (pin "A26") (pinfunction "A26_A26") (pintype "passive"))
      (node (ref "X4") (pin "A26") (pinfunction "A26_A26") (pintype "passive"))
    )
  )
)
